# AD7124.net
KiCad netlist of a schematic drawn in Altium Designer
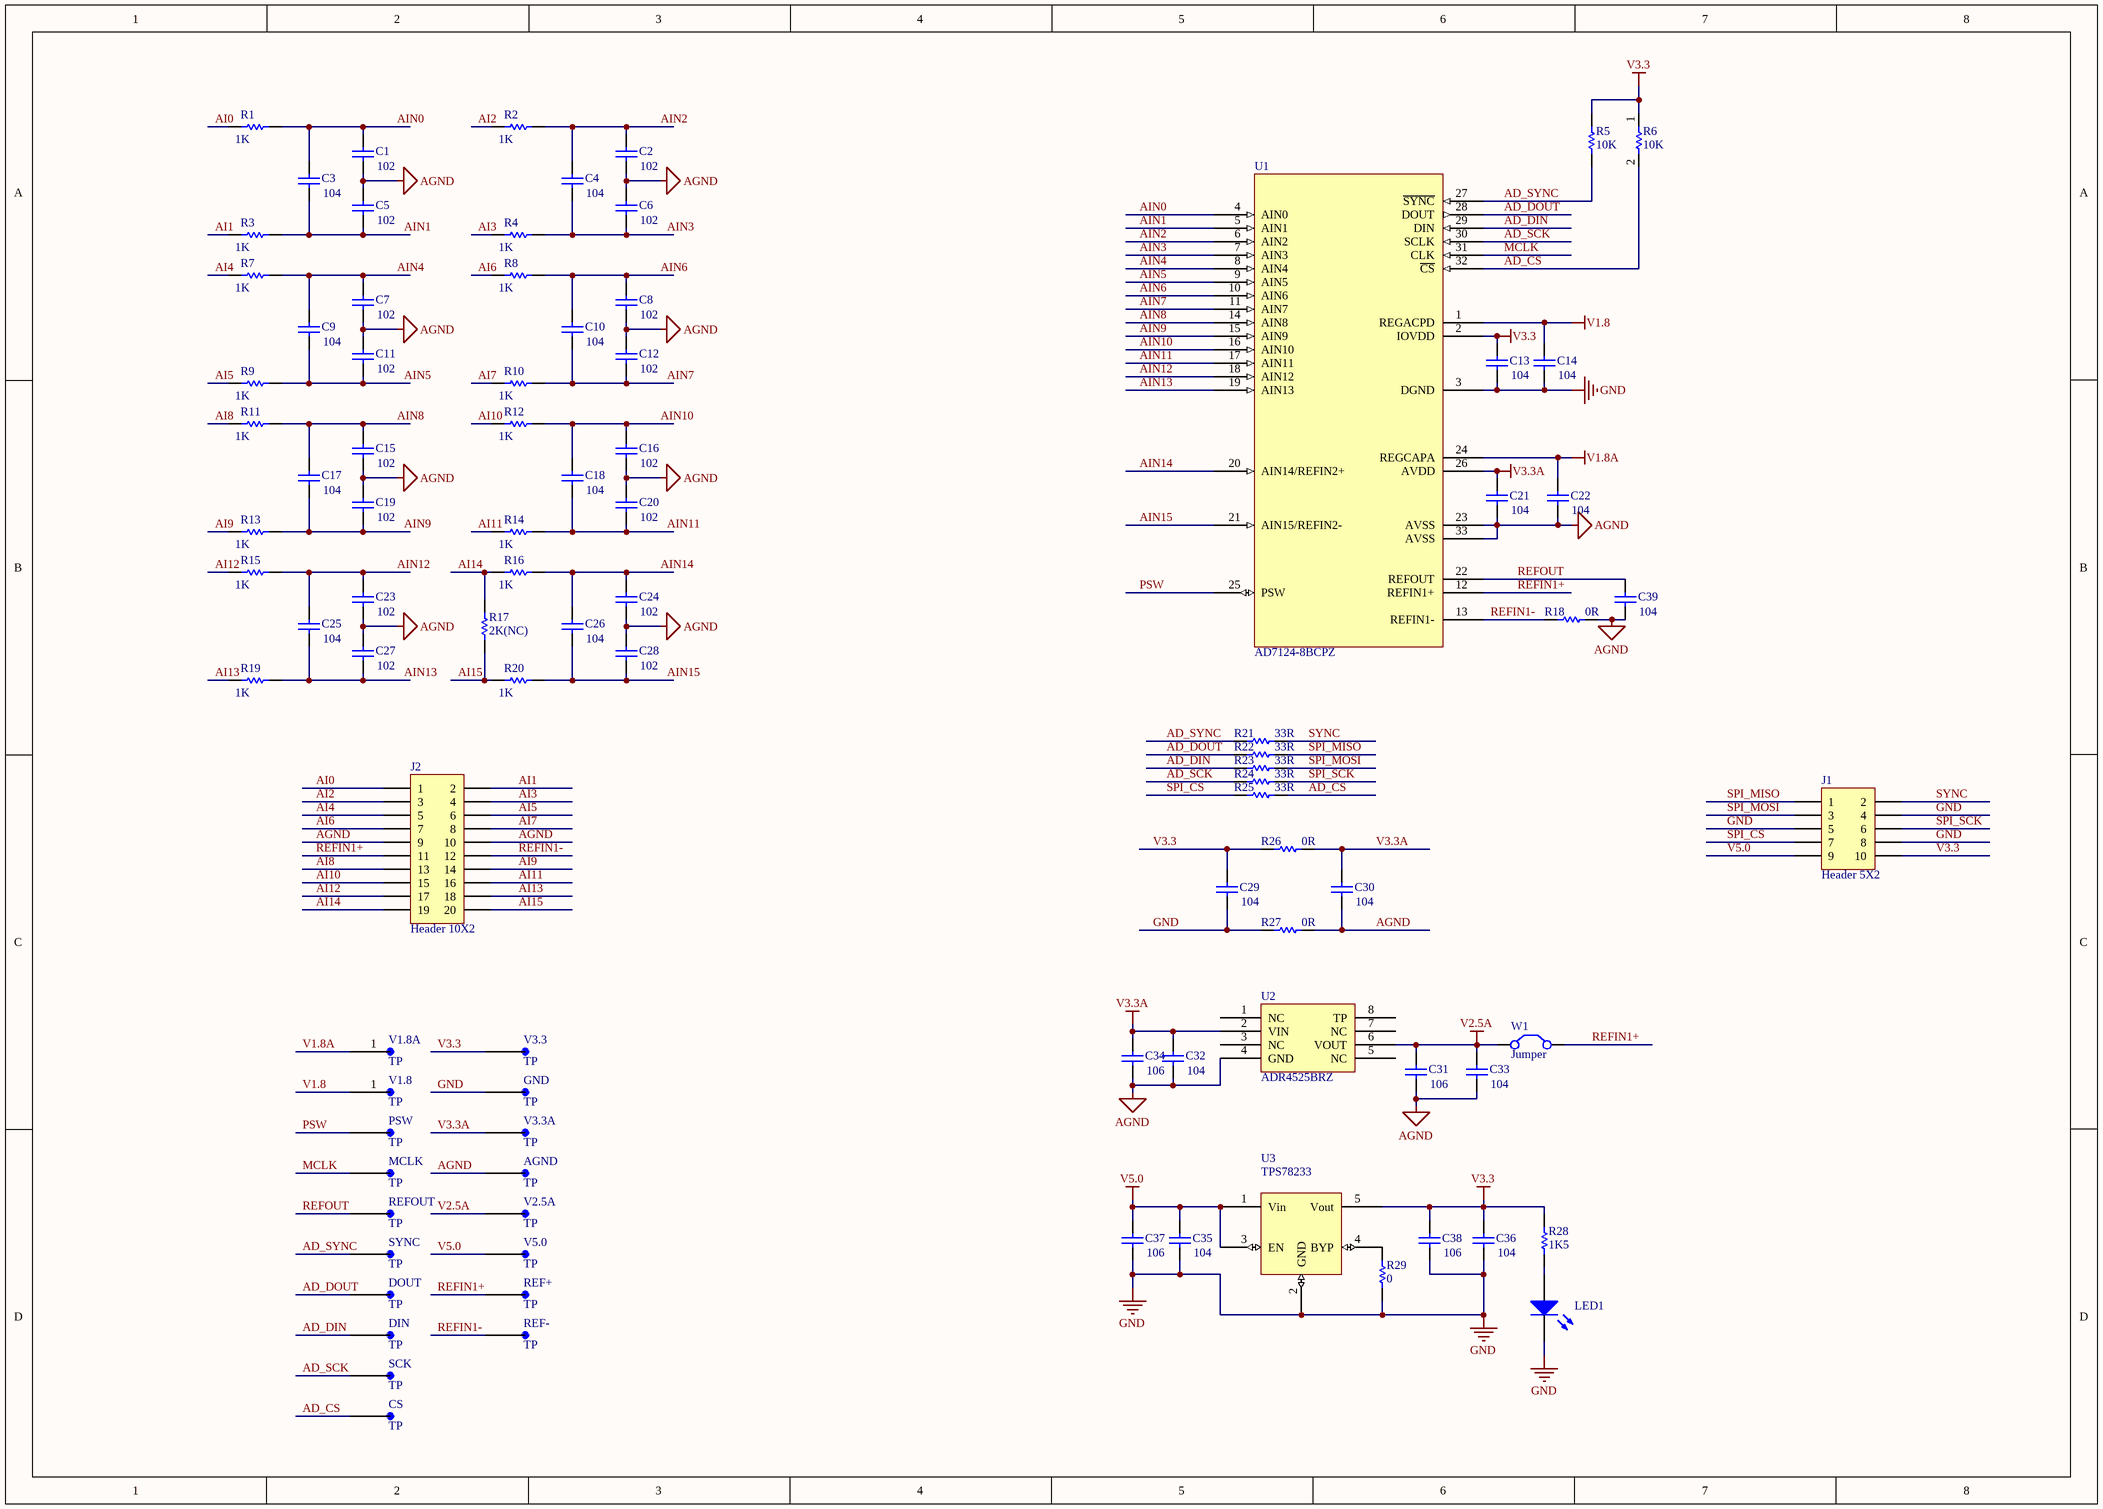
[diagram p0: AD7124.SchDoc]

(export (version "E")
  (design (tool "Eeschema 10.0.6"))
  (components
    (comp (ref "AGND")
      (value "TP")
      (footprint "TP -DRILL")
      (libsource (lib "AD7124原理图库") (part "Single_Hole"))
    )
    (comp (ref "C1")
      (value "102")
      (footprint "C0603")
      (description "Capacitor")
      (fields (field (name "Comment") "15pF") (field (name "PUBLISHER") "Altium Limited"))
      (libsource (lib "Miscellaneous Devices") (part "Cap"))
    )
    (comp (ref "C2")
      (value "102")
      (footprint "C0603")
      (description "Capacitor")
      (fields (field (name "Comment") "15pF") (field (name "PUBLISHER") "Altium Limited"))
      (libsource (lib "Miscellaneous Devices") (part "Cap"))
    )
    (comp (ref "C3")
      (value "104")
      (footprint "C0603")
      (description "Capacitor")
      (fields (field (name "Comment") "15pF") (field (name "PUBLISHER") "Altium Limited"))
      (libsource (lib "Miscellaneous Devices") (part "Cap"))
    )
    (comp (ref "C4")
      (value "104")
      (footprint "C0603")
      (description "Capacitor")
      (fields (field (name "Comment") "15pF") (field (name "PUBLISHER") "Altium Limited"))
      (libsource (lib "Miscellaneous Devices") (part "Cap"))
    )
    (comp (ref "C5")
      (value "102")
      (footprint "C0603")
      (description "Capacitor")
      (fields (field (name "Comment") "15pF") (field (name "PUBLISHER") "Altium Limited"))
      (libsource (lib "Miscellaneous Devices") (part "Cap"))
    )
    (comp (ref "C6")
      (value "102")
      (footprint "C0603")
      (description "Capacitor")
      (fields (field (name "Comment") "15pF") (field (name "PUBLISHER") "Altium Limited"))
      (libsource (lib "Miscellaneous Devices") (part "Cap"))
    )
    (comp (ref "C7")
      (value "102")
      (footprint "C0603")
      (description "Capacitor")
      (fields (field (name "Comment") "15pF") (field (name "PUBLISHER") "Altium Limited"))
      (libsource (lib "Miscellaneous Devices") (part "Cap"))
    )
    (comp (ref "C8")
      (value "102")
      (footprint "C0603")
      (description "Capacitor")
      (fields (field (name "Comment") "15pF") (field (name "PUBLISHER") "Altium Limited"))
      (libsource (lib "Miscellaneous Devices") (part "Cap"))
    )
    (comp (ref "C9")
      (value "104")
      (footprint "C0603")
      (description "Capacitor")
      (fields (field (name "Comment") "15pF") (field (name "PUBLISHER") "Altium Limited"))
      (libsource (lib "Miscellaneous Devices") (part "Cap"))
    )
    (comp (ref "C10")
      (value "104")
      (footprint "C0603")
      (description "Capacitor")
      (fields (field (name "Comment") "15pF") (field (name "PUBLISHER") "Altium Limited"))
      (libsource (lib "Miscellaneous Devices") (part "Cap"))
    )
    (comp (ref "C11")
      (value "102")
      (footprint "C0603")
      (description "Capacitor")
      (fields (field (name "Comment") "15pF") (field (name "PUBLISHER") "Altium Limited"))
      (libsource (lib "Miscellaneous Devices") (part "Cap"))
    )
    (comp (ref "C12")
      (value "102")
      (footprint "C0603")
      (description "Capacitor")
      (fields (field (name "Comment") "15pF") (field (name "PUBLISHER") "Altium Limited"))
      (libsource (lib "Miscellaneous Devices") (part "Cap"))
    )
    (comp (ref "C13")
      (value "104")
      (footprint "C0603")
      (description "Capacitor")
      (fields (field (name "Comment") "15pF") (field (name "PUBLISHER") "Altium Limited"))
      (libsource (lib "Miscellaneous Devices") (part "Cap"))
    )
    (comp (ref "C14")
      (value "104")
      (footprint "C0603")
      (description "Capacitor")
      (fields (field (name "Comment") "15pF") (field (name "PUBLISHER") "Altium Limited"))
      (libsource (lib "Miscellaneous Devices") (part "Cap"))
    )
    (comp (ref "C15")
      (value "102")
      (footprint "C0603")
      (description "Capacitor")
      (fields (field (name "Comment") "15pF") (field (name "PUBLISHER") "Altium Limited"))
      (libsource (lib "Miscellaneous Devices") (part "Cap"))
    )
    (comp (ref "C16")
      (value "102")
      (footprint "C0603")
      (description "Capacitor")
      (fields (field (name "Comment") "15pF") (field (name "PUBLISHER") "Altium Limited"))
      (libsource (lib "Miscellaneous Devices") (part "Cap"))
    )
    (comp (ref "C17")
      (value "104")
      (footprint "C0603")
      (description "Capacitor")
      (fields (field (name "Comment") "15pF") (field (name "PUBLISHER") "Altium Limited"))
      (libsource (lib "Miscellaneous Devices") (part "Cap"))
    )
    (comp (ref "C18")
      (value "104")
      (footprint "C0603")
      (description "Capacitor")
      (fields (field (name "Comment") "15pF") (field (name "PUBLISHER") "Altium Limited"))
      (libsource (lib "Miscellaneous Devices") (part "Cap"))
    )
    (comp (ref "C19")
      (value "102")
      (footprint "C0603")
      (description "Capacitor")
      (fields (field (name "Comment") "15pF") (field (name "PUBLISHER") "Altium Limited"))
      (libsource (lib "Miscellaneous Devices") (part "Cap"))
    )
    (comp (ref "C20")
      (value "102")
      (footprint "C0603")
      (description "Capacitor")
      (fields (field (name "Comment") "15pF") (field (name "PUBLISHER") "Altium Limited"))
      (libsource (lib "Miscellaneous Devices") (part "Cap"))
    )
    (comp (ref "C21")
      (value "104")
      (footprint "C0603")
      (description "Capacitor")
      (fields (field (name "Comment") "15pF") (field (name "PUBLISHER") "Altium Limited"))
      (libsource (lib "Miscellaneous Devices") (part "Cap"))
    )
    (comp (ref "C22")
      (value "104")
      (footprint "C0603")
      (description "Capacitor")
      (fields (field (name "Comment") "15pF") (field (name "PUBLISHER") "Altium Limited"))
      (libsource (lib "Miscellaneous Devices") (part "Cap"))
    )
    (comp (ref "C23")
      (value "102")
      (footprint "C0603")
      (description "Capacitor")
      (fields (field (name "Comment") "15pF") (field (name "PUBLISHER") "Altium Limited"))
      (libsource (lib "Miscellaneous Devices") (part "Cap"))
    )
    (comp (ref "C24")
      (value "102")
      (footprint "C0603")
      (description "Capacitor")
      (fields (field (name "Comment") "15pF") (field (name "PUBLISHER") "Altium Limited"))
      (libsource (lib "Miscellaneous Devices") (part "Cap"))
    )
    (comp (ref "C25")
      (value "104")
      (footprint "C0603")
      (description "Capacitor")
      (fields (field (name "Comment") "15pF") (field (name "PUBLISHER") "Altium Limited"))
      (libsource (lib "Miscellaneous Devices") (part "Cap"))
    )
    (comp (ref "C26")
      (value "104")
      (footprint "C0603")
      (description "Capacitor")
      (fields (field (name "Comment") "15pF") (field (name "PUBLISHER") "Altium Limited"))
      (libsource (lib "Miscellaneous Devices") (part "Cap"))
    )
    (comp (ref "C27")
      (value "102")
      (footprint "C0603")
      (description "Capacitor")
      (fields (field (name "Comment") "15pF") (field (name "PUBLISHER") "Altium Limited"))
      (libsource (lib "Miscellaneous Devices") (part "Cap"))
    )
    (comp (ref "C28")
      (value "102")
      (footprint "C0603")
      (description "Capacitor")
      (fields (field (name "Comment") "15pF") (field (name "PUBLISHER") "Altium Limited"))
      (libsource (lib "Miscellaneous Devices") (part "Cap"))
    )
    (comp (ref "C29")
      (value "104")
      (footprint "C0603")
      (description "Capacitor")
      (fields (field (name "Comment") "15pF") (field (name "PUBLISHER") "Altium Limited"))
      (libsource (lib "Miscellaneous Devices") (part "Cap"))
    )
    (comp (ref "C30")
      (value "104")
      (footprint "C0603")
      (description "Capacitor")
      (fields (field (name "Comment") "15pF") (field (name "PUBLISHER") "Altium Limited"))
      (libsource (lib "Miscellaneous Devices") (part "Cap"))
    )
    (comp (ref "C31")
      (value "106")
      (footprint "C1206")
      (description "Capacitor")
      (fields (field (name "Comment") "15pF") (field (name "PUBLISHER") "Altium Limited"))
      (libsource (lib "Miscellaneous Devices") (part "Cap"))
    )
    (comp (ref "C32")
      (value "104")
      (footprint "C0603")
      (description "Capacitor")
      (fields (field (name "Comment") "15pF") (field (name "PUBLISHER") "Altium Limited"))
      (libsource (lib "Miscellaneous Devices") (part "Cap"))
    )
    (comp (ref "C33")
      (value "104")
      (footprint "C0603")
      (description "Capacitor")
      (fields (field (name "Comment") "15pF") (field (name "PUBLISHER") "Altium Limited"))
      (libsource (lib "Miscellaneous Devices") (part "Cap"))
    )
    (comp (ref "C34")
      (value "106")
      (footprint "C1206")
      (description "Capacitor")
      (fields (field (name "Comment") "15pF") (field (name "PUBLISHER") "Altium Limited"))
      (libsource (lib "Miscellaneous Devices") (part "Cap"))
    )
    (comp (ref "C35")
      (value "104")
      (footprint "C0603")
      (description "Capacitor")
      (fields (field (name "Comment") "15pF") (field (name "PUBLISHER") "Altium Limited"))
      (libsource (lib "Miscellaneous Devices") (part "Cap"))
    )
    (comp (ref "C36")
      (value "104")
      (footprint "C0603")
      (description "Capacitor")
      (fields (field (name "Comment") "15pF") (field (name "PUBLISHER") "Altium Limited"))
      (libsource (lib "Miscellaneous Devices") (part "Cap"))
    )
    (comp (ref "C37")
      (value "106")
      (footprint "C1206")
      (description "Capacitor")
      (fields (field (name "Comment") "15pF") (field (name "PUBLISHER") "Altium Limited"))
      (libsource (lib "Miscellaneous Devices") (part "Cap"))
    )
    (comp (ref "C38")
      (value "106")
      (footprint "C1206")
      (description "Capacitor")
      (fields (field (name "Comment") "15pF") (field (name "PUBLISHER") "Altium Limited"))
      (libsource (lib "Miscellaneous Devices") (part "Cap"))
    )
    (comp (ref "C39")
      (value "104")
      (footprint "C0603")
      (description "Capacitor")
      (fields (field (name "Comment") "15pF") (field (name "PUBLISHER") "Altium Limited"))
      (libsource (lib "Miscellaneous Devices") (part "Cap"))
    )
    (comp (ref "CS") (value "TP") (footprint "TP -DRILL") (libsource (lib "AD7124原理图库") (part "Single_Hole")))
    (comp (ref "DIN")
      (value "TP")
      (footprint "TP -DRILL")
      (libsource (lib "AD7124原理图库") (part "Single_Hole"))
    )
    (comp (ref "DOUT")
      (value "TP")
      (footprint "TP -DRILL")
      (libsource (lib "AD7124原理图库") (part "Single_Hole"))
    )
    (comp (ref "GND")
      (value "TP")
      (footprint "TP -DRILL")
      (libsource (lib "AD7124原理图库") (part "Single_Hole"))
    )
    (comp (ref "J1")
      (value "Header 5X2")
      (footprint "IDC10M")
      (description "Header, 5-Pin, Dual row")
      (fields (field (name "PUBLISHER") "Altium Limited"))
      (libsource (lib "Miscellaneous Connectors") (part "Header 5X2"))
    )
    (comp (ref "J2")
      (value "Header 10X2")
      (footprint "IDC20M")
      (description "Header, 10-Pin, Dual row")
      (fields (field (name "PUBLISHER") "Altium Limited"))
      (libsource (lib "Miscellaneous Connectors") (part "Header 10X2"))
    )
    (comp (ref "LED1")
      (value "LED1")
      (footprint "D0805")
      (description "Typical RED, GREEN, YELLOW, AMBER GaAs LED")
      (fields (field (name "PUBLISHER") "Altium Limited"))
      (libsource (lib "Miscellaneous Devices") (part "LED2"))
    )
    (comp (ref "MCLK")
      (value "TP")
      (footprint "TP -DRILL")
      (libsource (lib "AD7124原理图库") (part "Single_Hole"))
    )
    (comp (ref "PSW")
      (value "TP")
      (footprint "TP -DRILL")
      (libsource (lib "AD7124原理图库") (part "Single_Hole"))
    )
    (comp (ref "R1")
      (value "1K")
      (footprint "R0603")
      (description "Resistor")
      (fields (field (name "PUBLISHER") "Altium Limited"))
      (libsource (lib "Miscellaneous Devices") (part "Res1"))
    )
    (comp (ref "R2")
      (value "1K")
      (footprint "R0603")
      (description "Resistor")
      (fields (field (name "PUBLISHER") "Altium Limited"))
      (libsource (lib "Miscellaneous Devices") (part "Res1"))
    )
    (comp (ref "R3")
      (value "1K")
      (footprint "R0603")
      (description "Resistor")
      (fields (field (name "PUBLISHER") "Altium Limited"))
      (libsource (lib "Miscellaneous Devices") (part "Res1"))
    )
    (comp (ref "R4")
      (value "1K")
      (footprint "R0603")
      (description "Resistor")
      (fields (field (name "PUBLISHER") "Altium Limited"))
      (libsource (lib "Miscellaneous Devices") (part "Res1"))
    )
    (comp (ref "R5")
      (value "10K")
      (footprint "R0603")
      (description "Resistor")
      (fields (field (name "PUBLISHER") "Altium Limited"))
      (libsource (lib "Miscellaneous Devices") (part "Res1"))
    )
    (comp (ref "R6")
      (value "10K")
      (footprint "R0603")
      (description "Resistor")
      (fields (field (name "PUBLISHER") "Altium Limited"))
      (libsource (lib "") (part "Res1_2"))
    )
    (comp (ref "R7")
      (value "1K")
      (footprint "R0603")
      (description "Resistor")
      (fields (field (name "PUBLISHER") "Altium Limited"))
      (libsource (lib "Miscellaneous Devices") (part "Res1"))
    )
    (comp (ref "R8")
      (value "1K")
      (footprint "R0603")
      (description "Resistor")
      (fields (field (name "PUBLISHER") "Altium Limited"))
      (libsource (lib "Miscellaneous Devices") (part "Res1"))
    )
    (comp (ref "R9")
      (value "1K")
      (footprint "R0603")
      (description "Resistor")
      (fields (field (name "PUBLISHER") "Altium Limited"))
      (libsource (lib "Miscellaneous Devices") (part "Res1"))
    )
    (comp (ref "R10")
      (value "1K")
      (footprint "R0603")
      (description "Resistor")
      (fields (field (name "PUBLISHER") "Altium Limited"))
      (libsource (lib "Miscellaneous Devices") (part "Res1"))
    )
    (comp (ref "R11")
      (value "1K")
      (footprint "R0603")
      (description "Resistor")
      (fields (field (name "PUBLISHER") "Altium Limited"))
      (libsource (lib "Miscellaneous Devices") (part "Res1"))
    )
    (comp (ref "R12")
      (value "1K")
      (footprint "R0603")
      (description "Resistor")
      (fields (field (name "PUBLISHER") "Altium Limited"))
      (libsource (lib "Miscellaneous Devices") (part "Res1"))
    )
    (comp (ref "R13")
      (value "1K")
      (footprint "R0603")
      (description "Resistor")
      (fields (field (name "PUBLISHER") "Altium Limited"))
      (libsource (lib "Miscellaneous Devices") (part "Res1"))
    )
    (comp (ref "R14")
      (value "1K")
      (footprint "R0603")
      (description "Resistor")
      (fields (field (name "PUBLISHER") "Altium Limited"))
      (libsource (lib "Miscellaneous Devices") (part "Res1"))
    )
    (comp (ref "R15")
      (value "1K")
      (footprint "R0603")
      (description "Resistor")
      (fields (field (name "PUBLISHER") "Altium Limited"))
      (libsource (lib "Miscellaneous Devices") (part "Res1"))
    )
    (comp (ref "R16")
      (value "1K")
      (footprint "R0603")
      (description "Resistor")
      (fields (field (name "PUBLISHER") "Altium Limited"))
      (libsource (lib "Miscellaneous Devices") (part "Res1"))
    )
    (comp (ref "R17")
      (value "2K(NC)")
      (footprint "R1206")
      (description "Resistor")
      (fields (field (name "PUBLISHER") "Altium Limited"))
      (libsource (lib "Miscellaneous Devices") (part "Res1"))
    )
    (comp (ref "R18")
      (value "0R")
      (footprint "R1206")
      (description "Resistor")
      (fields (field (name "PUBLISHER") "Altium Limited"))
      (libsource (lib "Miscellaneous Devices") (part "Res1"))
    )
    (comp (ref "R19")
      (value "1K")
      (footprint "R0603")
      (description "Resistor")
      (fields (field (name "PUBLISHER") "Altium Limited"))
      (libsource (lib "Miscellaneous Devices") (part "Res1"))
    )
    (comp (ref "R20")
      (value "1K")
      (footprint "R0603")
      (description "Resistor")
      (fields (field (name "PUBLISHER") "Altium Limited"))
      (libsource (lib "Miscellaneous Devices") (part "Res1"))
    )
    (comp (ref "R21")
      (value "33R")
      (footprint "R0603")
      (description "Resistor")
      (fields (field (name "PUBLISHER") "Altium Limited"))
      (libsource (lib "Miscellaneous Devices") (part "Res1"))
    )
    (comp (ref "R22")
      (value "33R")
      (footprint "R0603")
      (description "Resistor")
      (fields (field (name "PUBLISHER") "Altium Limited"))
      (libsource (lib "") (part "Res1_1"))
    )
    (comp (ref "R23")
      (value "33R")
      (footprint "R0603")
      (description "Resistor")
      (fields (field (name "PUBLISHER") "Altium Limited"))
      (libsource (lib "") (part "Res1_1"))
    )
    (comp (ref "R24")
      (value "33R")
      (footprint "R0603")
      (description "Resistor")
      (fields (field (name "PUBLISHER") "Altium Limited"))
      (libsource (lib "") (part "Res1_1"))
    )
    (comp (ref "R25")
      (value "33R")
      (footprint "R0603")
      (description "Resistor")
      (fields (field (name "PUBLISHER") "Altium Limited"))
      (libsource (lib "") (part "Res1_1"))
    )
    (comp (ref "R26")
      (value "0R")
      (footprint "R1206")
      (description "Resistor")
      (fields (field (name "PUBLISHER") "Altium Limited"))
      (libsource (lib "Miscellaneous Devices") (part "Res1"))
    )
    (comp (ref "R27")
      (value "0R")
      (footprint "R1206")
      (description "Resistor")
      (fields (field (name "PUBLISHER") "Altium Limited"))
      (libsource (lib "Miscellaneous Devices") (part "Res1"))
    )
    (comp (ref "R28")
      (value "1K5")
      (footprint "R0603")
      (description "Resistor")
      (fields (field (name "PUBLISHER") "Altium Limited"))
      (libsource (lib "") (part "Res1_1"))
    )
    (comp (ref "R29")
      (value "0")
      (footprint "R0603")
      (description "Resistor")
      (fields (field (name "PUBLISHER") "Altium Limited"))
      (libsource (lib "") (part "Res1_1"))
    )
    (comp (ref "REF+")
      (value "TP")
      (footprint "TP -DRILL")
      (libsource (lib "AD7124原理图库") (part "Single_Hole"))
    )
    (comp (ref "REF-")
      (value "TP")
      (footprint "TP -DRILL")
      (libsource (lib "AD7124原理图库") (part "Single_Hole"))
    )
    (comp (ref "REFOUT")
      (value "TP")
      (footprint "TP -DRILL")
      (libsource (lib "AD7124原理图库") (part "Single_Hole"))
    )
    (comp (ref "SCK")
      (value "TP")
      (footprint "TP -DRILL")
      (libsource (lib "AD7124原理图库") (part "Single_Hole"))
    )
    (comp (ref "SYNC")
      (value "TP")
      (footprint "TP -DRILL")
      (libsource (lib "AD7124原理图库") (part "Single_Hole"))
    )
    (comp (ref "U1")
      (value "AD7124-8BCPZ")
      (footprint "QFN32")
      (libsource (lib "AD7124原理图库") (part "AD7124-8BCPZ"))
    )
    (comp (ref "U2")
      (value "ADR4525BRZ")
      (footprint "SO-8")
      (libsource (lib "AD7124原理图库") (part "ADR4525BRZ"))
    )
    (comp (ref "U3") (value "TPS78233") (footprint "SOT-23-5") (libsource (lib "*") (part "CAT6219-330")))
    (comp (ref "V1.8") (value "TP") (footprint "TP -DRILL") (libsource (lib "") (part "Single_Hole_1")))
    (comp (ref "V1.8A") (value "TP") (footprint "TP -DRILL") (libsource (lib "") (part "Single_Hole_1")))
    (comp (ref "V2.5A")
      (value "TP")
      (footprint "TP -DRILL")
      (libsource (lib "AD7124原理图库") (part "Single_Hole"))
    )
    (comp (ref "V3.3")
      (value "TP")
      (footprint "TP -DRILL")
      (libsource (lib "AD7124原理图库") (part "Single_Hole"))
    )
    (comp (ref "V3.3A")
      (value "TP")
      (footprint "TP -DRILL")
      (libsource (lib "AD7124原理图库") (part "Single_Hole"))
    )
    (comp (ref "V5.0")
      (value "TP")
      (footprint "TP -DRILL")
      (libsource (lib "AD7124原理图库") (part "Single_Hole"))
    )
    (comp (ref "W1")
      (value "Jumper")
      (footprint "HDR1X2")
      (description "Jumper Wire")
      (fields (field (name "PUBLISHER") "Altium Limited"))
      (libsource (lib "Miscellaneous Devices") (part "Jumper"))
    )
  )
  (nets
    (net (code "1") (name "/AD_CS") (class "Default")
      (node (ref "CS") (pin "1") (pinfunction "9_1") (pintype "passive"))
      (node (ref "R25") (pin "2") (pinfunction "2_2") (pintype "passive"))
      (node (ref "R6") (pin "2") (pinfunction "1_2") (pintype "passive"))
      (node (ref "U1") (pin "32") (pinfunction "~{CS}_32") (pintype "input"))
    )
    (net (code "2") (name "/AD_DIN") (class "Default")
      (node (ref "DIN") (pin "1") (pinfunction "9_1") (pintype "passive"))
      (node (ref "R23") (pin "2") (pinfunction "2_2") (pintype "passive"))
      (node (ref "U1") (pin "29") (pinfunction "DIN_29") (pintype "input"))
    )
    (net (code "3") (name "/AD_DOUT") (class "Default")
      (node (ref "DOUT") (pin "1") (pinfunction "9_1") (pintype "passive"))
      (node (ref "R22") (pin "2") (pinfunction "2_2") (pintype "passive"))
      (node (ref "U1") (pin "28") (pinfunction "DOUT_28") (pintype "output"))
    )
    (net (code "4") (name "/AD_SCK") (class "Default")
      (node (ref "R24") (pin "2") (pinfunction "2_2") (pintype "passive"))
      (node (ref "SCK") (pin "1") (pinfunction "9_1") (pintype "passive"))
      (node (ref "U1") (pin "30") (pinfunction "SCLK_30") (pintype "input"))
    )
    (net (code "5") (name "/AD_SYNC") (class "Default")
      (node (ref "R21") (pin "2") (pinfunction "2_2") (pintype "passive"))
      (node (ref "R5") (pin "2") (pinfunction "2_2") (pintype "passive"))
      (node (ref "SYNC") (pin "1") (pinfunction "9_1") (pintype "passive"))
      (node (ref "U1") (pin "27") (pinfunction "~{SYNC}_27") (pintype "input"))
    )
    (net (code "6") (name "/AI0") (class "Default")
      (node (ref "J2") (pin "1") (pinfunction "1_1") (pintype "passive"))
      (node (ref "R1") (pin "2") (pinfunction "2_2") (pintype "passive"))
    )
    (net (code "7") (name "/AI1") (class "Default")
      (node (ref "J2") (pin "2") (pinfunction "2_2") (pintype "passive"))
      (node (ref "R3") (pin "2") (pinfunction "2_2") (pintype "passive"))
    )
    (net (code "8") (name "/AI2") (class "Default")
      (node (ref "J2") (pin "3") (pinfunction "3_3") (pintype "passive"))
      (node (ref "R2") (pin "2") (pinfunction "2_2") (pintype "passive"))
    )
    (net (code "9") (name "/AI3") (class "Default")
      (node (ref "J2") (pin "4") (pinfunction "4_4") (pintype "passive"))
      (node (ref "R4") (pin "2") (pinfunction "2_2") (pintype "passive"))
    )
    (net (code "10") (name "/AI4") (class "Default")
      (node (ref "J2") (pin "5") (pinfunction "5_5") (pintype "passive"))
      (node (ref "R7") (pin "2") (pinfunction "2_2") (pintype "passive"))
    )
    (net (code "11") (name "/AI5") (class "Default")
      (node (ref "J2") (pin "6") (pinfunction "6_6") (pintype "passive"))
      (node (ref "R9") (pin "2") (pinfunction "2_2") (pintype "passive"))
    )
    (net (code "12") (name "/AI6") (class "Default")
      (node (ref "J2") (pin "7") (pinfunction "7_7") (pintype "passive"))
      (node (ref "R8") (pin "2") (pinfunction "2_2") (pintype "passive"))
    )
    (net (code "13") (name "/AI7") (class "Default")
      (node (ref "J2") (pin "8") (pinfunction "8_8") (pintype "passive"))
      (node (ref "R10") (pin "2") (pinfunction "2_2") (pintype "passive"))
    )
    (net (code "14") (name "/AI8") (class "Default")
      (node (ref "J2") (pin "13") (pinfunction "13_13") (pintype "passive"))
      (node (ref "R11") (pin "2") (pinfunction "2_2") (pintype "passive"))
    )
    (net (code "15") (name "/AI9") (class "Default")
      (node (ref "J2") (pin "14") (pinfunction "14_14") (pintype "passive"))
      (node (ref "R13") (pin "2") (pinfunction "2_2") (pintype "passive"))
    )
    (net (code "16") (name "/AI10") (class "Default")
      (node (ref "J2") (pin "15") (pinfunction "15_15") (pintype "passive"))
      (node (ref "R12") (pin "2") (pinfunction "2_2") (pintype "passive"))
    )
    (net (code "17") (name "/AI11") (class "Default")
      (node (ref "J2") (pin "16") (pinfunction "16_16") (pintype "passive"))
      (node (ref "R14") (pin "2") (pinfunction "2_2") (pintype "passive"))
    )
    (net (code "18") (name "/AI12") (class "Default")
      (node (ref "J2") (pin "17") (pinfunction "17_17") (pintype "passive"))
      (node (ref "R15") (pin "2") (pinfunction "2_2") (pintype "passive"))
    )
    (net (code "19") (name "/AI13") (class "Default")
      (node (ref "J2") (pin "18") (pinfunction "18_18") (pintype "passive"))
      (node (ref "R19") (pin "2") (pinfunction "2_2") (pintype "passive"))
    )
    (net (code "20") (name "/AI14") (class "Default")
      (node (ref "J2") (pin "19") (pinfunction "19_19") (pintype "passive"))
      (node (ref "R16") (pin "2") (pinfunction "2_2") (pintype "passive"))
      (node (ref "R17") (pin "1") (pinfunction "1_1") (pintype "passive"))
    )
    (net (code "21") (name "/AI15") (class "Default")
      (node (ref "J2") (pin "20") (pinfunction "20_20") (pintype "passive"))
      (node (ref "R17") (pin "2") (pinfunction "2_2") (pintype "passive"))
      (node (ref "R20") (pin "2") (pinfunction "2_2") (pintype "passive"))
    )
    (net (code "22") (name "/AIN0") (class "Default")
      (node (ref "C1") (pin "2") (pinfunction "2_2") (pintype "passive"))
      (node (ref "C3") (pin "2") (pinfunction "2_2") (pintype "passive"))
      (node (ref "R1") (pin "1") (pinfunction "1_1") (pintype "passive"))
      (node (ref "U1") (pin "4") (pinfunction "AIN0_4") (pintype "input"))
    )
    (net (code "23") (name "/AIN1") (class "Default")
      (node (ref "C3") (pin "1") (pinfunction "1_1") (pintype "passive"))
      (node (ref "C5") (pin "1") (pinfunction "1_1") (pintype "passive"))
      (node (ref "R3") (pin "1") (pinfunction "1_1") (pintype "passive"))
      (node (ref "U1") (pin "5") (pinfunction "AIN1_5") (pintype "input"))
    )
    (net (code "24") (name "/AIN2") (class "Default")
      (node (ref "C2") (pin "2") (pinfunction "2_2") (pintype "passive"))
      (node (ref "C4") (pin "2") (pinfunction "2_2") (pintype "passive"))
      (node (ref "R2") (pin "1") (pinfunction "1_1") (pintype "passive"))
      (node (ref "U1") (pin "6") (pinfunction "AIN2_6") (pintype "input"))
    )
    (net (code "25") (name "/AIN3") (class "Default")
      (node (ref "C4") (pin "1") (pinfunction "1_1") (pintype "passive"))
      (node (ref "C6") (pin "1") (pinfunction "1_1") (pintype "passive"))
      (node (ref "R4") (pin "1") (pinfunction "1_1") (pintype "passive"))
      (node (ref "U1") (pin "7") (pinfunction "AIN3_7") (pintype "input"))
    )
    (net (code "26") (name "/AIN4") (class "Default")
      (node (ref "C7") (pin "2") (pinfunction "2_2") (pintype "passive"))
      (node (ref "C9") (pin "2") (pinfunction "2_2") (pintype "passive"))
      (node (ref "R7") (pin "1") (pinfunction "1_1") (pintype "passive"))
      (node (ref "U1") (pin "8") (pinfunction "AIN4_8") (pintype "input"))
    )
    (net (code "27") (name "/AIN5") (class "Default")
      (node (ref "C11") (pin "1") (pinfunction "1_1") (pintype "passive"))
      (node (ref "C9") (pin "1") (pinfunction "1_1") (pintype "passive"))
      (node (ref "R9") (pin "1") (pinfunction "1_1") (pintype "passive"))
      (node (ref "U1") (pin "9") (pinfunction "AIN5_9") (pintype "input"))
    )
    (net (code "28") (name "/AIN6") (class "Default")
      (node (ref "C10") (pin "2") (pinfunction "2_2") (pintype "passive"))
      (node (ref "C8") (pin "2") (pinfunction "2_2") (pintype "passive"))
      (node (ref "R8") (pin "1") (pinfunction "1_1") (pintype "passive"))
      (node (ref "U1") (pin "10") (pinfunction "AIN6_10") (pintype "input"))
    )
    (net (code "29") (name "/AIN7") (class "Default")
      (node (ref "C10") (pin "1") (pinfunction "1_1") (pintype "passive"))
      (node (ref "C12") (pin "1") (pinfunction "1_1") (pintype "passive"))
      (node (ref "R10") (pin "1") (pinfunction "1_1") (pintype "passive"))
      (node (ref "U1") (pin "11") (pinfunction "AIN7_11") (pintype "input"))
    )
    (net (code "30") (name "/AIN8") (class "Default")
      (node (ref "C15") (pin "2") (pinfunction "2_2") (pintype "passive"))
      (node (ref "C17") (pin "2") (pinfunction "2_2") (pintype "passive"))
      (node (ref "R11") (pin "1") (pinfunction "1_1") (pintype "passive"))
      (node (ref "U1") (pin "14") (pinfunction "AIN8_14") (pintype "input"))
    )
    (net (code "31") (name "/AIN9") (class "Default")
      (node (ref "C17") (pin "1") (pinfunction "1_1") (pintype "passive"))
      (node (ref "C19") (pin "1") (pinfunction "1_1") (pintype "passive"))
      (node (ref "R13") (pin "1") (pinfunction "1_1") (pintype "passive"))
      (node (ref "U1") (pin "15") (pinfunction "AIN9_15") (pintype "input"))
    )
    (net (code "32") (name "/AIN10") (class "Default")
      (node (ref "C16") (pin "2") (pinfunction "2_2") (pintype "passive"))
      (node (ref "C18") (pin "2") (pinfunction "2_2") (pintype "passive"))
      (node (ref "R12") (pin "1") (pinfunction "1_1") (pintype "passive"))
      (node (ref "U1") (pin "16") (pinfunction "AIN10_16") (pintype "input"))
    )
    (net (code "33") (name "/AIN11") (class "Default")
      (node (ref "C18") (pin "1") (pinfunction "1_1") (pintype "passive"))
      (node (ref "C20") (pin "1") (pinfunction "1_1") (pintype "passive"))
      (node (ref "R14") (pin "1") (pinfunction "1_1") (pintype "passive"))
      (node (ref "U1") (pin "17") (pinfunction "AIN11_17") (pintype "input"))
    )
    (net (code "34") (name "/AIN12") (class "Default")
      (node (ref "C23") (pin "2") (pinfunction "2_2") (pintype "passive"))
      (node (ref "C25") (pin "2") (pinfunction "2_2") (pintype "passive"))
      (node (ref "R15") (pin "1") (pinfunction "1_1") (pintype "passive"))
      (node (ref "U1") (pin "18") (pinfunction "AIN12_18") (pintype "input"))
    )
    (net (code "35") (name "/AIN13") (class "Default")
      (node (ref "C25") (pin "1") (pinfunction "1_1") (pintype "passive"))
      (node (ref "C27") (pin "1") (pinfunction "1_1") (pintype "passive"))
      (node (ref "R19") (pin "1") (pinfunction "1_1") (pintype "passive"))
      (node (ref "U1") (pin "19") (pinfunction "AIN13_19") (pintype "input"))
    )
    (net (code "36") (name "/AIN14") (class "Default")
      (node (ref "C24") (pin "2") (pinfunction "2_2") (pintype "passive"))
      (node (ref "C26") (pin "2") (pinfunction "2_2") (pintype "passive"))
      (node (ref "R16") (pin "1") (pinfunction "1_1") (pintype "passive"))
      (node (ref "U1") (pin "20") (pinfunction "AIN14/REFIN2+_20") (pintype "input"))
    )
    (net (code "37") (name "/AIN15") (class "Default")
      (node (ref "C26") (pin "1") (pinfunction "1_1") (pintype "passive"))
      (node (ref "C28") (pin "1") (pinfunction "1_1") (pintype "passive"))
      (node (ref "R20") (pin "1") (pinfunction "1_1") (pintype "passive"))
      (node (ref "U1") (pin "21") (pinfunction "AIN15/REFIN2-_21") (pintype "input"))
    )
    (net (code "38") (name "/MCLK") (class "Default")
      (node (ref "MCLK") (pin "1") (pinfunction "9_1") (pintype "passive"))
      (node (ref "U1") (pin "31") (pinfunction "CLK_31") (pintype "input"))
    )
    (net (code "39") (name "/PSW") (class "Default")
      (node (ref "PSW") (pin "1") (pinfunction "9_1") (pintype "passive"))
      (node (ref "U1") (pin "25") (pinfunction "PSW_25") (pintype "bidirectional"))
    )
    (net (code "40") (name "/REFIN1+") (class "Default")
      (node (ref "J2") (pin "11") (pinfunction "11_11") (pintype "passive"))
      (node (ref "REF+") (pin "1") (pinfunction "9_1") (pintype "passive"))
      (node (ref "U1") (pin "12") (pinfunction "REFIN1+_12") (pintype "passive"))
      (node (ref "W1") (pin "2") (pinfunction "C2_2") (pintype "passive"))
    )
    (net (code "41") (name "/REFIN1-") (class "Default")
      (node (ref "J2") (pin "12") (pinfunction "12_12") (pintype "passive"))
      (node (ref "R18") (pin "2") (pinfunction "2_2") (pintype "passive"))
      (node (ref "REF-") (pin "1") (pinfunction "9_1") (pintype "passive"))
      (node (ref "U1") (pin "13") (pinfunction "REFIN1-_13") (pintype "passive"))
    )
    (net (code "42") (name "/REFOUT") (class "Default")
      (node (ref "C39") (pin "2") (pinfunction "2_2") (pintype "passive"))
      (node (ref "REFOUT") (pin "1") (pinfunction "9_1") (pintype "passive"))
      (node (ref "U1") (pin "22") (pinfunction "REFOUT_22") (pintype "passive"))
    )
    (net (code "43") (name "/SPI_CS") (class "Default")
      (node (ref "J1") (pin "7") (pinfunction "7_7") (pintype "passive"))
      (node (ref "R25") (pin "1") (pinfunction "1_1") (pintype "passive"))
    )
    (net (code "44") (name "/SPI_MISO") (class "Default")
      (node (ref "J1") (pin "1") (pinfunction "1_1") (pintype "passive"))
      (node (ref "R22") (pin "1") (pinfunction "1_1") (pintype "passive"))
    )
    (net (code "45") (name "/SPI_MOSI") (class "Default")
      (node (ref "J1") (pin "3") (pinfunction "3_3") (pintype "passive"))
      (node (ref "R23") (pin "1") (pinfunction "1_1") (pintype "passive"))
    )
    (net (code "46") (name "/SPI_SCK") (class "Default")
      (node (ref "J1") (pin "6") (pinfunction "6_6") (pintype "passive"))
      (node (ref "R24") (pin "1") (pinfunction "1_1") (pintype "passive"))
    )
    (net (code "47") (name "/SYNC") (class "Default")
      (node (ref "J1") (pin "2") (pinfunction "2_2") (pintype "passive"))
      (node (ref "R21") (pin "1") (pinfunction "1_1") (pintype "passive"))
    )
    (net (code "48") (name "AGND") (class "Default")
      (node (ref "AGND") (pin "1") (pinfunction "9_1") (pintype "passive"))
      (node (ref "C1") (pin "1") (pinfunction "1_1") (pintype "passive"))
      (node (ref "C11") (pin "2") (pinfunction "2_2") (pintype "passive"))
      (node (ref "C12") (pin "2") (pinfunction "2_2") (pintype "passive"))
      (node (ref "C15") (pin "1") (pinfunction "1_1") (pintype "passive"))
      (node (ref "C16") (pin "1") (pinfunction "1_1") (pintype "passive"))
      (node (ref "C19") (pin "2") (pinfunction "2_2") (pintype "passive"))
      (node (ref "C2") (pin "1") (pinfunction "1_1") (pintype "passive"))
      (node (ref "C20") (pin "2") (pinfunction "2_2") (pintype "passive"))
      (node (ref "C21") (pin "1") (pinfunction "1_1") (pintype "passive"))
      (node (ref "C22") (pin "1") (pinfunction "1_1") (pintype "passive"))
      (node (ref "C23") (pin "1") (pinfunction "1_1") (pintype "passive"))
      (node (ref "C24") (pin "1") (pinfunction "1_1") (pintype "passive"))
      (node (ref "C27") (pin "2") (pinfunction "2_2") (pintype "passive"))
      (node (ref "C28") (pin "2") (pinfunction "2_2") (pintype "passive"))
      (node (ref "C30") (pin "1") (pinfunction "1_1") (pintype "passive"))
      (node (ref "C31") (pin "1") (pinfunction "1_1") (pintype "passive"))
      (node (ref "C32") (pin "1") (pinfunction "1_1") (pintype "passive"))
      (node (ref "C33") (pin "1") (pinfunction "1_1") (pintype "passive"))
      (node (ref "C34") (pin "1") (pinfunction "1_1") (pintype "passive"))
      (node (ref "C39") (pin "1") (pinfunction "1_1") (pintype "passive"))
      (node (ref "C5") (pin "2") (pinfunction "2_2") (pintype "passive"))
      (node (ref "C6") (pin "2") (pinfunction "2_2") (pintype "passive"))
      (node (ref "C7") (pin "1") (pinfunction "1_1") (pintype "passive"))
      (node (ref "C8") (pin "1") (pinfunction "1_1") (pintype "passive"))
      (node (ref "J2") (pin "10") (pinfunction "10_10") (pintype "passive"))
      (node (ref "J2") (pin "9") (pinfunction "9_9") (pintype "passive"))
      (node (ref "R18") (pin "1") (pinfunction "1_1") (pintype "passive"))
      (node (ref "R27") (pin "1") (pinfunction "1_1") (pintype "passive"))
      (node (ref "U1") (pin "23") (pinfunction "AVSS_23") (pintype "passive"))
      (node (ref "U1") (pin "33") (pinfunction "AVSS_33") (pintype "passive"))
      (node (ref "U2") (pin "4") (pinfunction "GND_4") (pintype "passive"))
    )
    (net (code "49") (name "GND") (class "Default")
      (node (ref "C13") (pin "1") (pinfunction "1_1") (pintype "passive"))
      (node (ref "C14") (pin "1") (pinfunction "1_1") (pintype "passive"))
      (node (ref "C29") (pin "1") (pinfunction "1_1") (pintype "passive"))
      (node (ref "C35") (pin "1") (pinfunction "1_1") (pintype "passive"))
      (node (ref "C36") (pin "1") (pinfunction "1_1") (pintype "passive"))
      (node (ref "C37") (pin "1") (pinfunction "1_1") (pintype "passive"))
      (node (ref "C38") (pin "1") (pinfunction "1_1") (pintype "passive"))
      (node (ref "GND") (pin "1") (pinfunction "9_1") (pintype "passive"))
      (node (ref "J1") (pin "4") (pinfunction "4_4") (pintype "passive"))
      (node (ref "J1") (pin "5") (pinfunction "5_5") (pintype "passive"))
      (node (ref "J1") (pin "8") (pinfunction "8_8") (pintype "passive"))
      (node (ref "LED1") (pin "2") (pinfunction "K_2") (pintype "passive"))
      (node (ref "R27") (pin "2") (pinfunction "2_2") (pintype "passive"))
      (node (ref "R29") (pin "1") (pinfunction "1_1") (pintype "passive"))
      (node (ref "U1") (pin "3") (pinfunction "DGND_3") (pintype "passive"))
      (node (ref "U3") (pin "2") (pinfunction "GND_2") (pintype "bidirectional"))
    )
    (net (code "50") (name "Net-(LED1-A)") (class "Default")
      (node (ref "LED1") (pin "1") (pinfunction "A_1") (pintype "passive"))
      (node (ref "R28") (pin "1") (pinfunction "1_1") (pintype "passive"))
    )
    (net (code "51") (name "Net-(U3-BYP)") (class "Default")
      (node (ref "R29") (pin "2") (pinfunction "2_2") (pintype "passive"))
      (node (ref "U3") (pin "4") (pinfunction "BYP_4") (pintype "bidirectional"))
    )
    (net (code "52") (name "V1.8") (class "Default")
      (node (ref "C14") (pin "2") (pinfunction "2_2") (pintype "passive"))
      (node (ref "U1") (pin "1") (pinfunction "REGACPD_1") (pintype "passive"))
      (node (ref "V1.8") (pin "1") (pinfunction "9_1") (pintype "passive"))
    )
    (net (code "53") (name "V1.8A") (class "Default")
      (node (ref "C22") (pin "2") (pinfunction "2_2") (pintype "passive"))
      (node (ref "U1") (pin "24") (pinfunction "REGCAPA_24") (pintype "passive"))
      (node (ref "V1.8A") (pin "1") (pinfunction "9_1") (pintype "passive"))
    )
    (net (code "54") (name "V2.5A") (class "Default")
      (node (ref "C31") (pin "2") (pinfunction "2_2") (pintype "passive"))
      (node (ref "C33") (pin "2") (pinfunction "2_2") (pintype "passive"))
      (node (ref "U2") (pin "6") (pinfunction "VOUT_6") (pintype "passive"))
      (node (ref "V2.5A") (pin "1") (pinfunction "9_1") (pintype "passive"))
      (node (ref "W1") (pin "1") (pinfunction "C1_1") (pintype "passive"))
    )
    (net (code "55") (name "V3.3") (class "Default")
      (node (ref "C13") (pin "2") (pinfunction "2_2") (pintype "passive"))
      (node (ref "C29") (pin "2") (pinfunction "2_2") (pintype "passive"))
      (node (ref "C36") (pin "2") (pinfunction "2_2") (pintype "passive"))
      (node (ref "C38") (pin "2") (pinfunction "2_2") (pintype "passive"))
      (node (ref "J1") (pin "10") (pinfunction "10_10") (pintype "passive"))
      (node (ref "R26") (pin "2") (pinfunction "2_2") (pintype "passive"))
      (node (ref "R28") (pin "2") (pinfunction "2_2") (pintype "passive"))
      (node (ref "R5") (pin "1") (pinfunction "1_1") (pintype "passive"))
      (node (ref "R6") (pin "1") (pinfunction "1_1") (pintype "passive"))
      (node (ref "U1") (pin "2") (pinfunction "IOVDD_2") (pintype "passive"))
      (node (ref "U3") (pin "5") (pinfunction "Vout_5") (pintype "power_in"))
      (node (ref "V3.3") (pin "1") (pinfunction "9_1") (pintype "passive"))
    )
    (net (code "56") (name "V3.3A") (class "Default")
      (node (ref "C21") (pin "2") (pinfunction "2_2") (pintype "passive"))
      (node (ref "C30") (pin "2") (pinfunction "2_2") (pintype "passive"))
      (node (ref "C32") (pin "2") (pinfunction "2_2") (pintype "passive"))
      (node (ref "C34") (pin "2") (pinfunction "2_2") (pintype "passive"))
      (node (ref "R26") (pin "1") (pinfunction "1_1") (pintype "passive"))
      (node (ref "U1") (pin "26") (pinfunction "AVDD_26") (pintype "passive"))
      (node (ref "U2") (pin "2") (pinfunction "VIN_2") (pintype "passive"))
      (node (ref "V3.3A") (pin "1") (pinfunction "9_1") (pintype "passive"))
    )
    (net (code "57") (name "V5.0") (class "Default")
      (node (ref "C35") (pin "2") (pinfunction "2_2") (pintype "passive"))
      (node (ref "C37") (pin "2") (pinfunction "2_2") (pintype "passive"))
      (node (ref "J1") (pin "9") (pinfunction "9_9") (pintype "passive"))
      (node (ref "U3") (pin "1") (pinfunction "Vin_1") (pintype "power_in"))
      (node (ref "U3") (pin "3") (pinfunction "EN_3") (pintype "bidirectional"))
      (node (ref "V5.0") (pin "1") (pinfunction "9_1") (pintype "passive"))
    )
    (net (code "58") (name "unconnected-(U2-NC-Pad1)") (class "Default")
      (node (ref "U2") (pin "1") (pinfunction "NC_1") (pintype "passive"))
    )
    (net (code "59") (name "unconnected-(U2-NC-Pad3)") (class "Default")
      (node (ref "U2") (pin "3") (pinfunction "NC_3") (pintype "passive"))
    )
    (net (code "60") (name "unconnected-(U2-NC-Pad5)") (class "Default")
      (node (ref "U2") (pin "5") (pinfunction "NC_5") (pintype "passive"))
    )
    (net (code "61") (name "unconnected-(U2-NC-Pad7)") (class "Default")
      (node (ref "U2") (pin "7") (pinfunction "NC_7") (pintype "passive"))
    )
    (net (code "62") (name "unconnected-(U2-TP-Pad8)") (class "Default")
      (node (ref "U2") (pin "8") (pinfunction "TP_8") (pintype "passive"))
    )
  )
)
